# LEDs.net
KiCad netlist of a schematic drawn in Altium Designer
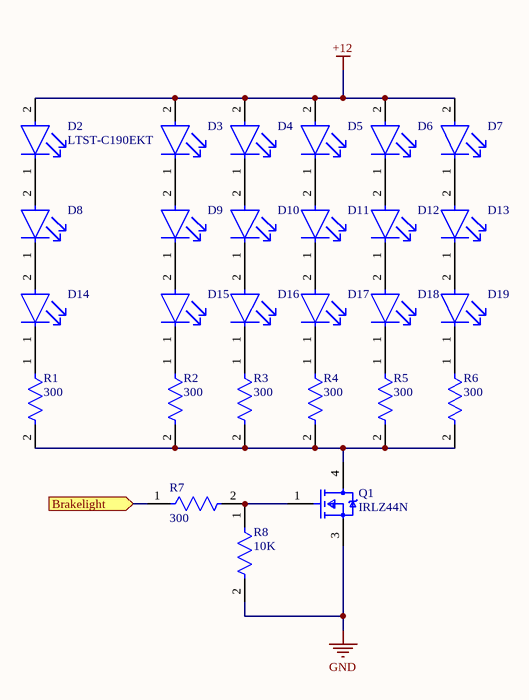
[diagram p0: LEDs.SchDoc]

(export (version "E")
  (design (tool "Eeschema 10.0.6"))
  (components
    (comp (ref "D2")
      (value "LTST-C190EKT")
      (footprint "FP-LTST-C190EKT-MFG")
      (description "LED RED CLEAR CHIP SMD")
      (libsource (lib "Altium Content Vault") (part "8706943c75ba83719d021d2fdc84c58"))
    )
    (comp (ref "D3")
      (value "LTST-C190EKT")
      (footprint "FP-LTST-C190EKT-MFG")
      (description "LED RED CLEAR CHIP SMD")
      (libsource (lib "Altium Content Vault") (part "8706943c75ba83719d021d2fdc84c58"))
    )
    (comp (ref "D4")
      (value "LTST-C190EKT")
      (footprint "FP-LTST-C190EKT-MFG")
      (description "LED RED CLEAR CHIP SMD")
      (libsource (lib "Altium Content Vault") (part "8706943c75ba83719d021d2fdc84c58"))
    )
    (comp (ref "D5")
      (value "LTST-C190EKT")
      (footprint "FP-LTST-C190EKT-MFG")
      (description "LED RED CLEAR CHIP SMD")
      (libsource (lib "Altium Content Vault") (part "8706943c75ba83719d021d2fdc84c58"))
    )
    (comp (ref "D6")
      (value "LTST-C190EKT")
      (footprint "FP-LTST-C190EKT-MFG")
      (description "LED RED CLEAR CHIP SMD")
      (libsource (lib "Altium Content Vault") (part "8706943c75ba83719d021d2fdc84c58"))
    )
    (comp (ref "D7")
      (value "LTST-C190EKT")
      (footprint "FP-LTST-C190EKT-MFG")
      (description "LED RED CLEAR CHIP SMD")
      (libsource (lib "Altium Content Vault") (part "8706943c75ba83719d021d2fdc84c58"))
    )
    (comp (ref "D8")
      (value "LTST-C190EKT")
      (footprint "FP-LTST-C190EKT-MFG")
      (description "LED RED CLEAR CHIP SMD")
      (libsource (lib "Altium Content Vault") (part "8706943c75ba83719d021d2fdc84c58"))
    )
    (comp (ref "D9")
      (value "LTST-C190EKT")
      (footprint "FP-LTST-C190EKT-MFG")
      (description "LED RED CLEAR CHIP SMD")
      (libsource (lib "Altium Content Vault") (part "8706943c75ba83719d021d2fdc84c58"))
    )
    (comp (ref "D10")
      (value "LTST-C190EKT")
      (footprint "FP-LTST-C190EKT-MFG")
      (description "LED RED CLEAR CHIP SMD")
      (libsource (lib "Altium Content Vault") (part "8706943c75ba83719d021d2fdc84c58"))
    )
    (comp (ref "D11")
      (value "LTST-C190EKT")
      (footprint "FP-LTST-C190EKT-MFG")
      (description "LED RED CLEAR CHIP SMD")
      (libsource (lib "Altium Content Vault") (part "8706943c75ba83719d021d2fdc84c58"))
    )
    (comp (ref "D12")
      (value "LTST-C190EKT")
      (footprint "FP-LTST-C190EKT-MFG")
      (description "LED RED CLEAR CHIP SMD")
      (libsource (lib "Altium Content Vault") (part "8706943c75ba83719d021d2fdc84c58"))
    )
    (comp (ref "D13")
      (value "LTST-C190EKT")
      (footprint "FP-LTST-C190EKT-MFG")
      (description "LED RED CLEAR CHIP SMD")
      (libsource (lib "Altium Content Vault") (part "8706943c75ba83719d021d2fdc84c58"))
    )
    (comp (ref "D14")
      (value "LTST-C190EKT")
      (footprint "FP-LTST-C190EKT-MFG")
      (description "LED RED CLEAR CHIP SMD")
      (libsource (lib "Altium Content Vault") (part "8706943c75ba83719d021d2fdc84c58"))
    )
    (comp (ref "D15")
      (value "LTST-C190EKT")
      (footprint "FP-LTST-C190EKT-MFG")
      (description "LED RED CLEAR CHIP SMD")
      (libsource (lib "Altium Content Vault") (part "8706943c75ba83719d021d2fdc84c58"))
    )
    (comp (ref "D16")
      (value "LTST-C190EKT")
      (footprint "FP-LTST-C190EKT-MFG")
      (description "LED RED CLEAR CHIP SMD")
      (libsource (lib "Altium Content Vault") (part "8706943c75ba83719d021d2fdc84c58"))
    )
    (comp (ref "D17")
      (value "LTST-C190EKT")
      (footprint "FP-LTST-C190EKT-MFG")
      (description "LED RED CLEAR CHIP SMD")
      (libsource (lib "Altium Content Vault") (part "8706943c75ba83719d021d2fdc84c58"))
    )
    (comp (ref "D18")
      (value "LTST-C190EKT")
      (footprint "FP-LTST-C190EKT-MFG")
      (description "LED RED CLEAR CHIP SMD")
      (libsource (lib "Altium Content Vault") (part "8706943c75ba83719d021d2fdc84c58"))
    )
    (comp (ref "D19")
      (value "LTST-C190EKT")
      (footprint "FP-LTST-C190EKT-MFG")
      (description "LED RED CLEAR CHIP SMD")
      (libsource (lib "Altium Content Vault") (part "8706943c75ba83719d021d2fdc84c58"))
    )
    (comp (ref "Q1")
      (value "IRLZ44N")
      (footprint "FP-PG-TO263-3-MFG")
      (description "MOSFET N-CH 55V 47A D2PAK")
      (libsource (lib "Altium Content Vault") (part "cdf1c68f84cb049e5ebc85739c3fcf6"))
    )
    (comp (ref "R1")
      (value "300")
      (footprint "FP-CRCW1206-e3-IPC_A")
      (description "RES Thick Film, 300Ω, 1%, 0.25W, 100ppm/°C, 1206")
      (fields (field (name "TOLERANCE") "1%"))
      (libsource (lib "Altium Content Vault") (part "1029c3af85768c4190bb7ad29bc67b5"))
    )
    (comp (ref "R2")
      (value "300")
      (footprint "FP-CRCW1206-e3-IPC_A")
      (description "RES Thick Film, 300Ω, 1%, 0.25W, 100ppm/°C, 1206")
      (fields (field (name "TOLERANCE") "1%"))
      (libsource (lib "Altium Content Vault") (part "1029c3af85768c4190bb7ad29bc67b5"))
    )
    (comp (ref "R3")
      (value "300")
      (footprint "FP-CRCW1206-e3-IPC_A")
      (description "RES Thick Film, 300Ω, 1%, 0.25W, 100ppm/°C, 1206")
      (fields (field (name "TOLERANCE") "1%"))
      (libsource (lib "Altium Content Vault") (part "1029c3af85768c4190bb7ad29bc67b5"))
    )
    (comp (ref "R4")
      (value "300")
      (footprint "FP-CRCW1206-e3-IPC_A")
      (description "RES Thick Film, 300Ω, 1%, 0.25W, 100ppm/°C, 1206")
      (fields (field (name "TOLERANCE") "1%"))
      (libsource (lib "Altium Content Vault") (part "1029c3af85768c4190bb7ad29bc67b5"))
    )
    (comp (ref "R5")
      (value "300")
      (footprint "FP-CRCW1206-e3-IPC_A")
      (description "RES Thick Film, 300Ω, 1%, 0.25W, 100ppm/°C, 1206")
      (fields (field (name "TOLERANCE") "1%"))
      (libsource (lib "Altium Content Vault") (part "1029c3af85768c4190bb7ad29bc67b5"))
    )
    (comp (ref "R6")
      (value "300")
      (footprint "FP-CRCW1206-e3-IPC_A")
      (description "RES Thick Film, 300Ω, 1%, 0.25W, 100ppm/°C, 1206")
      (fields (field (name "TOLERANCE") "1%"))
      (libsource (lib "Altium Content Vault") (part "1029c3af85768c4190bb7ad29bc67b5"))
    )
    (comp (ref "R7")
      (value "300")
      (footprint "FP-CRCW1206-e3-IPC_A")
      (description "RES Thick Film, 300Ω, 1%, 0.25W, 100ppm/°C, 1206")
      (fields (field (name "TOLERANCE") "1%"))
      (libsource (lib "Altium Content Vault") (part "1029c3af85768c4190bb7ad29bc67b5"))
    )
    (comp (ref "R8")
      (value "10K")
      (footprint "FP-CRCW0603-e3-IPC_B")
      (description "RES Thick Film, 10kΩ, 1%, 0.1W, 100ppm/°C, 0603")
      (fields (field (name "TOLERANCE") "1%"))
      (libsource (lib "Altium Content Vault") (part "1029c3af85768c4190bb7ad29bc67b5"))
    )
  )
  (nets
    (net (code "1") (name "+12") (class "Default")
      (node (ref "D2") (pin "2") (pinfunction "A_2") (pintype "passive"))
      (node (ref "D3") (pin "2") (pinfunction "A_2") (pintype "passive"))
      (node (ref "D4") (pin "2") (pinfunction "A_2") (pintype "passive"))
      (node (ref "D5") (pin "2") (pinfunction "A_2") (pintype "passive"))
      (node (ref "D6") (pin "2") (pinfunction "A_2") (pintype "passive"))
      (node (ref "D7") (pin "2") (pinfunction "A_2") (pintype "passive"))
    )
    (net (code "2") (name "/Brakelight") (class "Default")
      (node (ref "R7") (pin "1") (pinfunction "1_1") (pintype "passive"))
    )
    (net (code "3") (name "GND") (class "Default")
      (node (ref "Q1") (pin "3") (pinfunction "S_3") (pintype "passive"))
      (node (ref "R8") (pin "2") (pinfunction "2_2") (pintype "passive"))
    )
    (net (code "4") (name "Net-(D2-C)") (class "Default")
      (node (ref "D2") (pin "1") (pinfunction "C_1") (pintype "passive"))
      (node (ref "D8") (pin "2") (pinfunction "A_2") (pintype "passive"))
    )
    (net (code "5") (name "Net-(D3-C)") (class "Default")
      (node (ref "D3") (pin "1") (pinfunction "C_1") (pintype "passive"))
      (node (ref "D9") (pin "2") (pinfunction "A_2") (pintype "passive"))
    )
    (net (code "6") (name "Net-(D10-A)") (class "Default")
      (node (ref "D10") (pin "2") (pinfunction "A_2") (pintype "passive"))
      (node (ref "D4") (pin "1") (pinfunction "C_1") (pintype "passive"))
    )
    (net (code "7") (name "Net-(D10-C)") (class "Default")
      (node (ref "D10") (pin "1") (pinfunction "C_1") (pintype "passive"))
      (node (ref "D16") (pin "2") (pinfunction "A_2") (pintype "passive"))
    )
    (net (code "8") (name "Net-(D11-A)") (class "Default")
      (node (ref "D11") (pin "2") (pinfunction "A_2") (pintype "passive"))
      (node (ref "D5") (pin "1") (pinfunction "C_1") (pintype "passive"))
    )
    (net (code "9") (name "Net-(D11-C)") (class "Default")
      (node (ref "D11") (pin "1") (pinfunction "C_1") (pintype "passive"))
      (node (ref "D17") (pin "2") (pinfunction "A_2") (pintype "passive"))
    )
    (net (code "10") (name "Net-(D12-A)") (class "Default")
      (node (ref "D12") (pin "2") (pinfunction "A_2") (pintype "passive"))
      (node (ref "D6") (pin "1") (pinfunction "C_1") (pintype "passive"))
    )
    (net (code "11") (name "Net-(D12-C)") (class "Default")
      (node (ref "D12") (pin "1") (pinfunction "C_1") (pintype "passive"))
      (node (ref "D18") (pin "2") (pinfunction "A_2") (pintype "passive"))
    )
    (net (code "12") (name "Net-(D13-A)") (class "Default")
      (node (ref "D13") (pin "2") (pinfunction "A_2") (pintype "passive"))
      (node (ref "D7") (pin "1") (pinfunction "C_1") (pintype "passive"))
    )
    (net (code "13") (name "Net-(D13-C)") (class "Default")
      (node (ref "D13") (pin "1") (pinfunction "C_1") (pintype "passive"))
      (node (ref "D19") (pin "2") (pinfunction "A_2") (pintype "passive"))
    )
    (net (code "14") (name "Net-(D14-A)") (class "Default")
      (node (ref "D14") (pin "2") (pinfunction "A_2") (pintype "passive"))
      (node (ref "D8") (pin "1") (pinfunction "C_1") (pintype "passive"))
    )
    (net (code "15") (name "Net-(D14-C)") (class "Default")
      (node (ref "D14") (pin "1") (pinfunction "C_1") (pintype "passive"))
      (node (ref "R1") (pin "1") (pinfunction "1_1") (pintype "passive"))
    )
    (net (code "16") (name "Net-(D15-A)") (class "Default")
      (node (ref "D15") (pin "2") (pinfunction "A_2") (pintype "passive"))
      (node (ref "D9") (pin "1") (pinfunction "C_1") (pintype "passive"))
    )
    (net (code "17") (name "Net-(D15-C)") (class "Default")
      (node (ref "D15") (pin "1") (pinfunction "C_1") (pintype "passive"))
      (node (ref "R2") (pin "1") (pinfunction "1_1") (pintype "passive"))
    )
    (net (code "18") (name "Net-(D16-C)") (class "Default")
      (node (ref "D16") (pin "1") (pinfunction "C_1") (pintype "passive"))
      (node (ref "R3") (pin "1") (pinfunction "1_1") (pintype "passive"))
    )
    (net (code "19") (name "Net-(D17-C)") (class "Default")
      (node (ref "D17") (pin "1") (pinfunction "C_1") (pintype "passive"))
      (node (ref "R4") (pin "1") (pinfunction "1_1") (pintype "passive"))
    )
    (net (code "20") (name "Net-(D18-C)") (class "Default")
      (node (ref "D18") (pin "1") (pinfunction "C_1") (pintype "passive"))
      (node (ref "R5") (pin "1") (pinfunction "1_1") (pintype "passive"))
    )
    (net (code "21") (name "Net-(D19-C)") (class "Default")
      (node (ref "D19") (pin "1") (pinfunction "C_1") (pintype "passive"))
      (node (ref "R6") (pin "1") (pinfunction "1_1") (pintype "passive"))
    )
    (net (code "22") (name "Net-(Q1-D)") (class "Default")
      (node (ref "Q1") (pin "4") (pinfunction "D_4") (pintype "passive"))
      (node (ref "R1") (pin "2") (pinfunction "2_2") (pintype "passive"))
      (node (ref "R2") (pin "2") (pinfunction "2_2") (pintype "passive"))
      (node (ref "R3") (pin "2") (pinfunction "2_2") (pintype "passive"))
      (node (ref "R4") (pin "2") (pinfunction "2_2") (pintype "passive"))
      (node (ref "R5") (pin "2") (pinfunction "2_2") (pintype "passive"))
      (node (ref "R6") (pin "2") (pinfunction "2_2") (pintype "passive"))
    )
    (net (code "23") (name "Net-(Q1-G)") (class "Default")
      (node (ref "Q1") (pin "1") (pinfunction "G_1") (pintype "passive"))
      (node (ref "R7") (pin "2") (pinfunction "2_2") (pintype "passive"))
      (node (ref "R8") (pin "1") (pinfunction "1_1") (pintype "passive"))
    )
  )
)
